# orpheus_esp.net
KiCad netlist of a schematic drawn in EasyEDA Pro
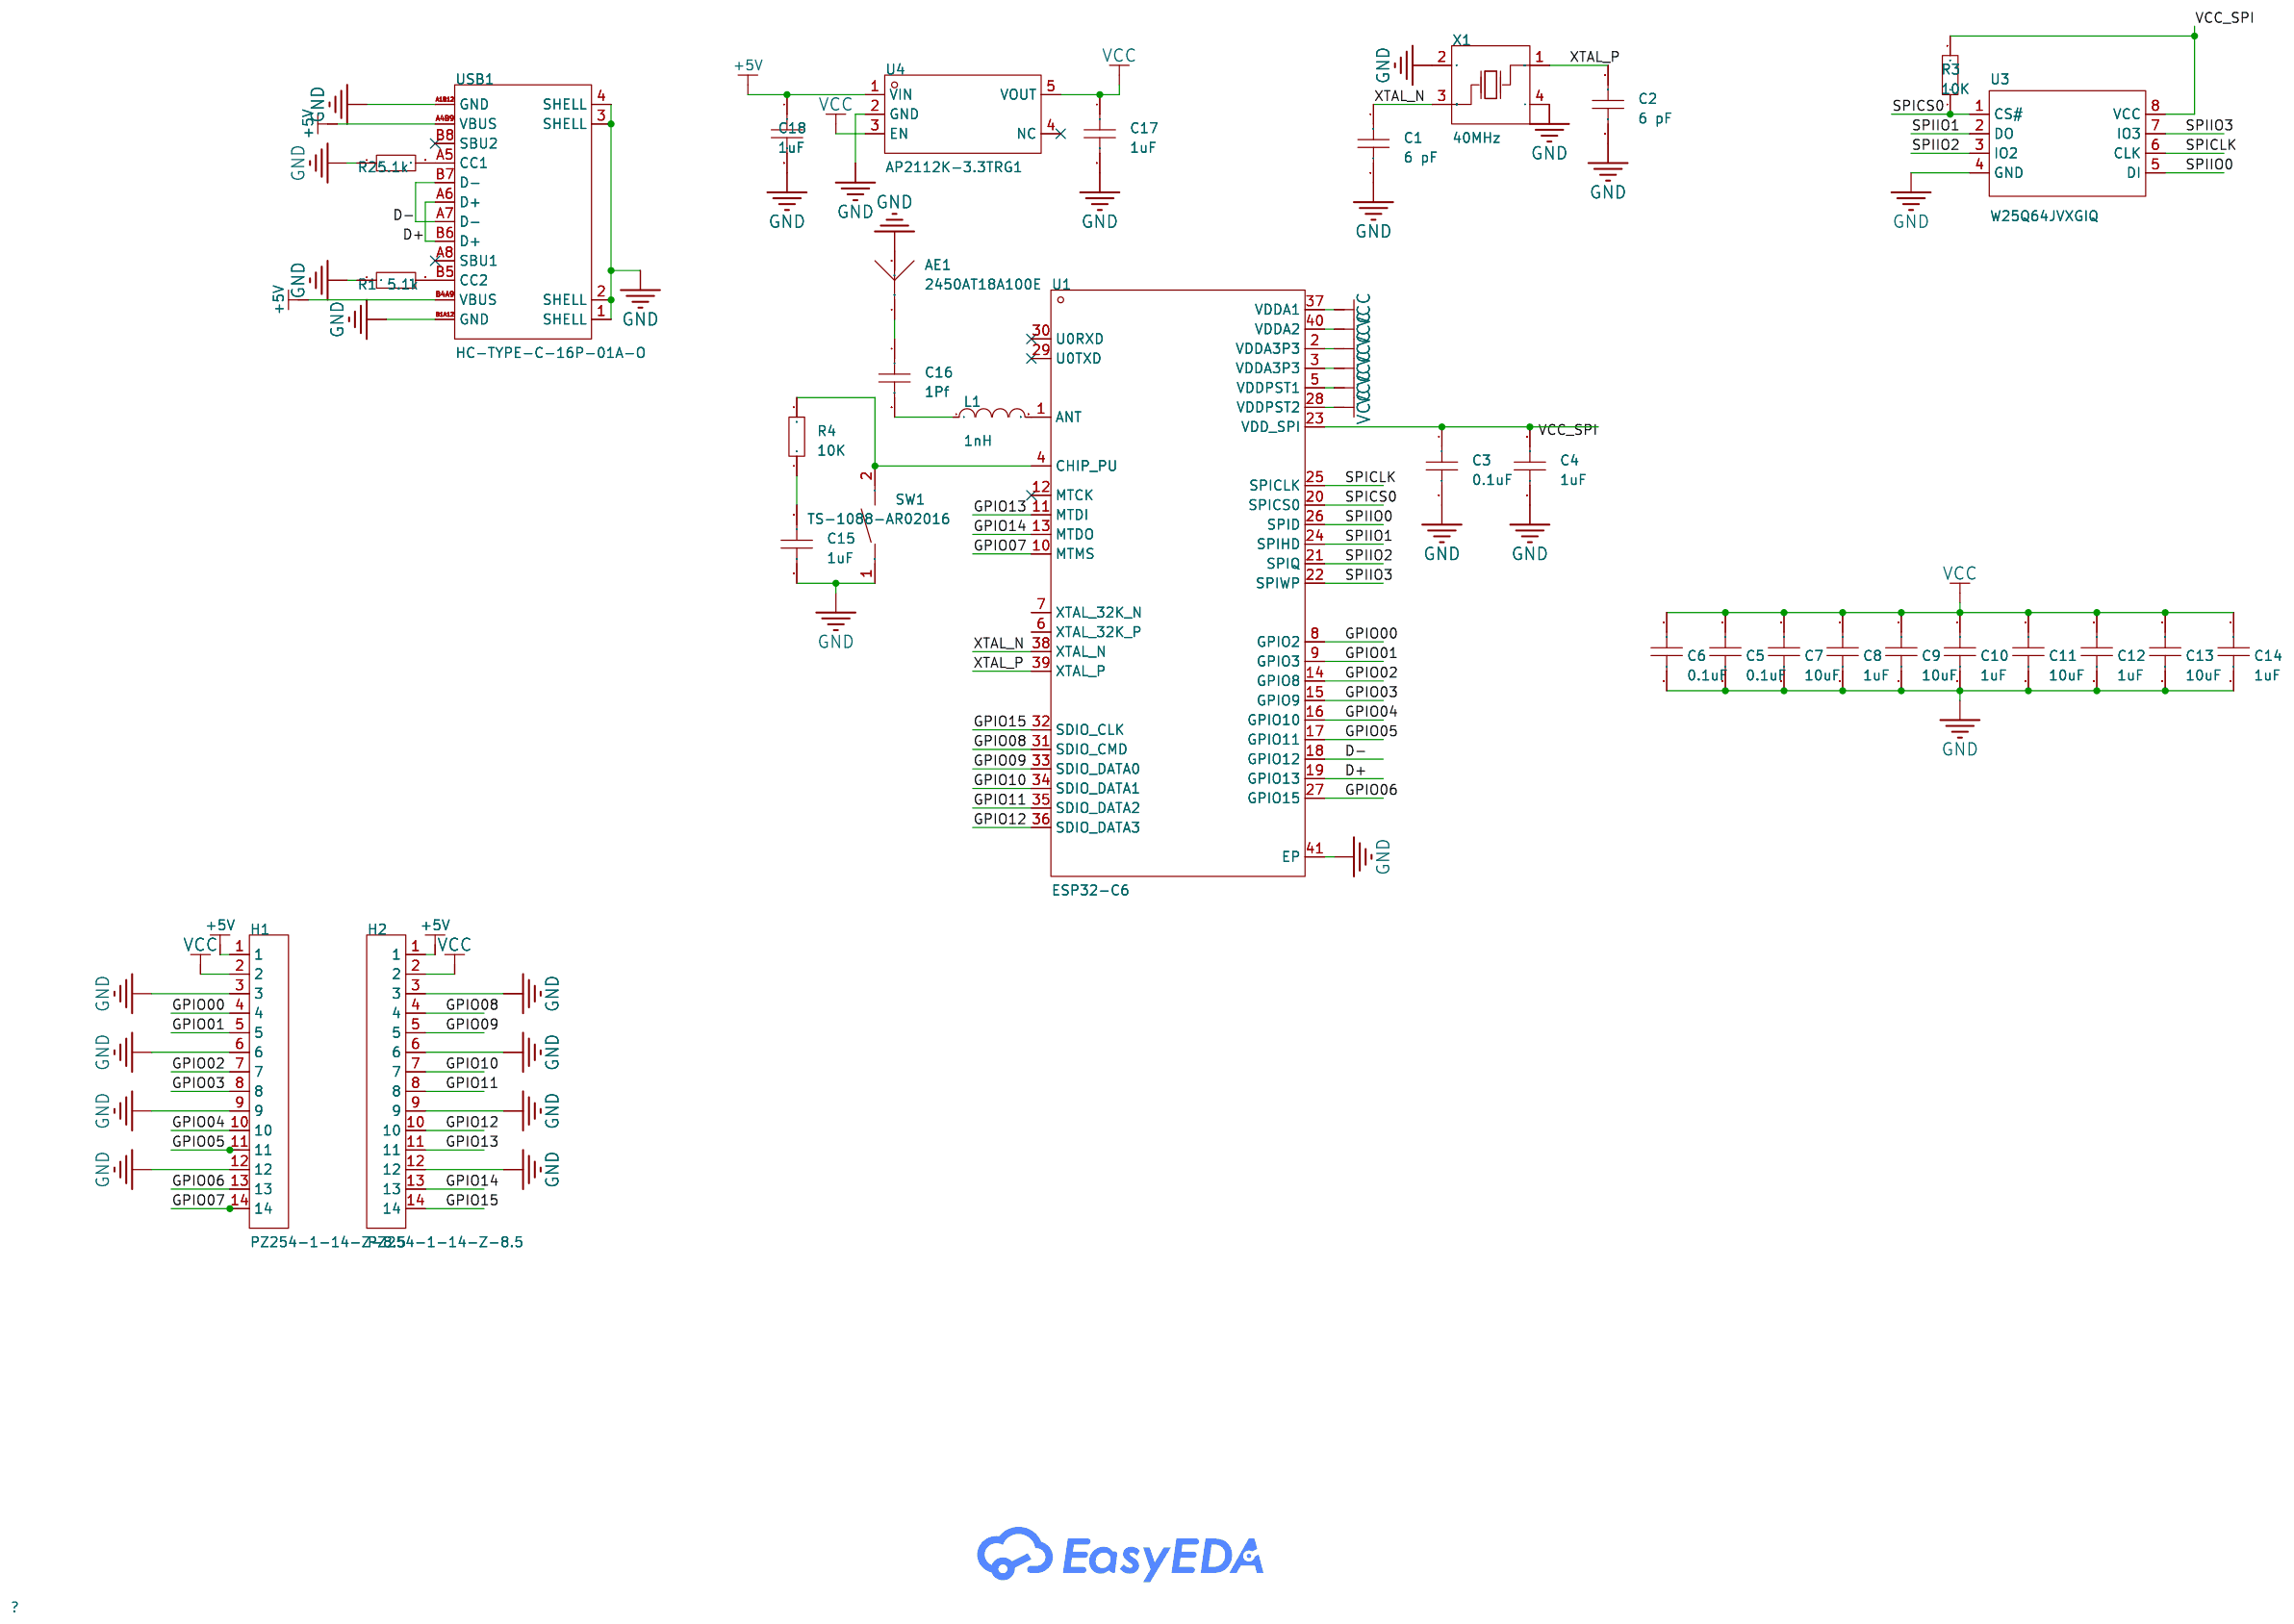
[diagram p0: schematic sheet]

(export (version "E")
  (design (tool "Eeschema 10.0.6"))
  (components
    (comp (ref "AE1")
      (value "2450AT18A100E")
      (footprint "easyedapro:ANT-SMD_L3.2-W1.6")
      (fields (field (name "Manufacturer") "JOHANSON(约翰逊)"))
      (libsource (lib "easyedapro") (part "2450AT18A100E"))
    )
    (comp (ref "C1")
      (value "6 pF")
      (footprint "easyedapro:C0603")
      (libsource (lib "easyedapro") (part "CAP"))
    )
    (comp (ref "C2")
      (value "6 pF")
      (footprint "easyedapro:C0603")
      (libsource (lib "easyedapro") (part "CAP"))
    )
    (comp (ref "C3")
      (value "0.1uF")
      (footprint "easyedapro:C0603")
      (libsource (lib "easyedapro") (part "CAP"))
    )
    (comp (ref "C4") (value "1uF") (footprint "easyedapro:C0603") (libsource (lib "easyedapro") (part "CAP")))
    (comp (ref "C5")
      (value "0.1uF")
      (footprint "easyedapro:C0603")
      (libsource (lib "easyedapro") (part "CAP"))
    )
    (comp (ref "C6")
      (value "0.1uF")
      (footprint "easyedapro:C0603")
      (libsource (lib "easyedapro") (part "CAP"))
    )
    (comp (ref "C7")
      (value "10uF")
      (footprint "easyedapro:C0603")
      (libsource (lib "easyedapro") (part "CAP"))
    )
    (comp (ref "C8") (value "1uF") (footprint "easyedapro:C0603") (libsource (lib "easyedapro") (part "CAP")))
    (comp (ref "C9")
      (value "10uF")
      (footprint "easyedapro:C0603")
      (libsource (lib "easyedapro") (part "CAP"))
    )
    (comp (ref "C10")
      (value "1uF")
      (footprint "easyedapro:C0603")
      (libsource (lib "easyedapro") (part "CAP"))
    )
    (comp (ref "C11")
      (value "10uF")
      (footprint "easyedapro:C0603")
      (libsource (lib "easyedapro") (part "CAP"))
    )
    (comp (ref "C12")
      (value "1uF")
      (footprint "easyedapro:C0603")
      (libsource (lib "easyedapro") (part "CAP"))
    )
    (comp (ref "C13")
      (value "10uF")
      (footprint "easyedapro:C0603")
      (libsource (lib "easyedapro") (part "CAP"))
    )
    (comp (ref "C14")
      (value "1uF")
      (footprint "easyedapro:C0603")
      (libsource (lib "easyedapro") (part "CAP"))
    )
    (comp (ref "C15")
      (value "1uF")
      (footprint "easyedapro:C0603")
      (libsource (lib "easyedapro") (part "CAP"))
    )
    (comp (ref "C16")
      (value "1Pf")
      (footprint "easyedapro:C0603")
      (libsource (lib "easyedapro") (part "CAP"))
    )
    (comp (ref "C17")
      (value "1uF")
      (footprint "easyedapro:C0603")
      (libsource (lib "easyedapro") (part "CAP"))
    )
    (comp (ref "C18")
      (value "1uF")
      (footprint "easyedapro:C0603")
      (libsource (lib "easyedapro") (part "CAP"))
    )
    (comp (ref "H1")
      (value "PZ254-1-14-Z-8.5")
      (footprint "easyedapro:HDR-TH_14P-P2.54-V-M")
      (fields (field (name "Manufacturer") "HCTL(华灿天禄)"))
      (libsource (lib "easyedapro") (part "PZ254-1-14-Z-8.5"))
    )
    (comp (ref "H2")
      (value "PZ254-1-14-Z-8.5")
      (footprint "easyedapro:HDR-TH_14P-P2.54-V-M")
      (fields (field (name "Manufacturer") "HCTL(华灿天禄)"))
      (libsource (lib "easyedapro") (part "PZ254-1-14-Z-8.5"))
    )
    (comp (ref "L1") (value "1nH") (footprint "easyedapro:L0603") (libsource (lib "easyedapro") (part "电感")))
    (comp (ref "R1")
      (value "5.1k")
      (footprint "easyedapro:R0603")
      (libsource (lib "easyedapro") (part "Res"))
    )
    (comp (ref "R2")
      (value "5.1k")
      (footprint "easyedapro:R0603")
      (libsource (lib "easyedapro") (part "Res"))
    )
    (comp (ref "R3") (value "10K") (footprint "easyedapro:R0603") (libsource (lib "easyedapro") (part "Res")))
    (comp (ref "R4") (value "10K") (footprint "easyedapro:R0603") (libsource (lib "easyedapro") (part "Res")))
    (comp (ref "SW1")
      (value "TS-1088-AR02016")
      (footprint "easyedapro:SW-SMD_L3.9-W3.0-P4.45")
      (fields (field (name "Manufacturer") "XUNPU(讯普)"))
      (libsource (lib "easyedapro") (part "TS-1088-AR02016"))
    )
    (comp (ref "U1")
      (value "ESP32-C6")
      (footprint "easyedapro:QFN-40_L5.0-W5.0-P0.40-TL-EP3.3")
      (fields (field (name "Manufacturer") "ESPRESSIF(乐鑫)"))
      (libsource (lib "easyedapro") (part "ESP32-C6_C5364646"))
    )
    (comp (ref "U3")
      (value "W25Q64JVXGIQ")
      (footprint "easyedapro:SOP-8_L5.3-W5.3-P1.27-LS8.0-BL")
      (fields (field (name "Manufacturer") "Winbond(华邦)"))
      (libsource (lib "easyedapro") (part "W25Q64JVSSIQ"))
    )
    (comp (ref "U4")
      (value "AP2112K-3.3TRG1")
      (footprint "easyedapro:SOT-25-5_L2.9-W1.6-P0.95-LS2.8-BL")
      (fields (field (name "Manufacturer") "DIODES(美台)"))
      (libsource (lib "easyedapro") (part "AP2112K-3.3TRG1"))
    )
    (comp (ref "USB1")
      (value "HC-TYPE-C-16P-01A-O")
      (footprint "easyedapro:USB-C-SMD_G-SWITCH_GT-USB-7010EN")
      (fields (field (name "Manufacturer") "HCTL(华灿天禄)"))
      (libsource (lib "easyedapro") (part "HC-TYPE-C-16P-01A-O"))
    )
    (comp (ref "X1")
      (value "40MHz")
      (footprint "easyedapro:CRYSTAL-SMD_4P-L2.0-W1.6-BL")
      (fields (field (name "Manufacturer Part") "Q22FA12800101") (field (name "Manufacturer") "EPSON(爱普生)"))
      (libsource (lib "easyedapro") (part "Q22FA12800101"))
    )
  )
  (nets
    (net (code "1") (name "+5V") (class "Default")
      (node (ref "C18") (pin "1") (pinfunction "1_1") (pintype "input"))
      (node (ref "H1") (pin "1") (pinfunction "1_1") (pintype "unspecified"))
      (node (ref "H2") (pin "1") (pinfunction "1_1") (pintype "unspecified"))
      (node (ref "U4") (pin "1") (pinfunction "VIN_1") (pintype "unspecified"))
      (node (ref "USB1") (pin "A4B9") (pinfunction "VBUS_A4B9") (pintype "unspecified"))
      (node (ref "USB1") (pin "B4A9") (pinfunction "VBUS_B4A9") (pintype "unspecified"))
    )
    (net (code "2") (name "/D+") (class "Default")
      (node (ref "U1") (pin "19") (pinfunction "GPIO13_19") (pintype "unspecified"))
      (node (ref "USB1") (pin "A6") (pinfunction "D+_A6") (pintype "unspecified"))
      (node (ref "USB1") (pin "B6") (pinfunction "D+_B6") (pintype "unspecified"))
    )
    (net (code "3") (name "/D-") (class "Default")
      (node (ref "U1") (pin "18") (pinfunction "GPIO12_18") (pintype "unspecified"))
      (node (ref "USB1") (pin "A7") (pinfunction "D-_A7") (pintype "unspecified"))
      (node (ref "USB1") (pin "B7") (pinfunction "D-_B7") (pintype "unspecified"))
    )
    (net (code "4") (name "/GPIO00") (class "Default")
      (node (ref "H1") (pin "4") (pinfunction "4_4") (pintype "unspecified"))
      (node (ref "U1") (pin "8") (pinfunction "GPIO2_8") (pintype "unspecified"))
    )
    (net (code "5") (name "/GPIO01") (class "Default")
      (node (ref "H1") (pin "5") (pinfunction "5_5") (pintype "unspecified"))
      (node (ref "U1") (pin "9") (pinfunction "GPIO3_9") (pintype "unspecified"))
    )
    (net (code "6") (name "/GPIO02") (class "Default")
      (node (ref "H1") (pin "7") (pinfunction "7_7") (pintype "unspecified"))
      (node (ref "U1") (pin "14") (pinfunction "GPIO8_14") (pintype "unspecified"))
    )
    (net (code "7") (name "/GPIO03") (class "Default")
      (node (ref "H1") (pin "8") (pinfunction "8_8") (pintype "unspecified"))
      (node (ref "U1") (pin "15") (pinfunction "GPIO9_15") (pintype "unspecified"))
    )
    (net (code "8") (name "/GPIO04") (class "Default")
      (node (ref "H1") (pin "10") (pinfunction "10_10") (pintype "unspecified"))
      (node (ref "U1") (pin "16") (pinfunction "GPIO10_16") (pintype "unspecified"))
    )
    (net (code "9") (name "/GPIO05") (class "Default")
      (node (ref "H1") (pin "11") (pinfunction "11_11") (pintype "unspecified"))
      (node (ref "U1") (pin "17") (pinfunction "GPIO11_17") (pintype "unspecified"))
    )
    (net (code "10") (name "/GPIO06") (class "Default")
      (node (ref "H1") (pin "13") (pinfunction "13_13") (pintype "unspecified"))
      (node (ref "U1") (pin "27") (pinfunction "GPIO15_27") (pintype "unspecified"))
    )
    (net (code "11") (name "/GPIO07") (class "Default")
      (node (ref "H1") (pin "14") (pinfunction "14_14") (pintype "unspecified"))
      (node (ref "U1") (pin "10") (pinfunction "MTMS_10") (pintype "unspecified"))
    )
    (net (code "12") (name "/GPIO08") (class "Default")
      (node (ref "H2") (pin "4") (pinfunction "4_4") (pintype "unspecified"))
      (node (ref "U1") (pin "31") (pinfunction "SDIO_CMD_31") (pintype "unspecified"))
    )
    (net (code "13") (name "/GPIO09") (class "Default")
      (node (ref "H2") (pin "5") (pinfunction "5_5") (pintype "unspecified"))
      (node (ref "U1") (pin "33") (pinfunction "SDIO_DATA0_33") (pintype "unspecified"))
    )
    (net (code "14") (name "/GPIO10") (class "Default")
      (node (ref "H2") (pin "7") (pinfunction "7_7") (pintype "unspecified"))
      (node (ref "U1") (pin "34") (pinfunction "SDIO_DATA1_34") (pintype "unspecified"))
    )
    (net (code "15") (name "/GPIO11") (class "Default")
      (node (ref "H2") (pin "8") (pinfunction "8_8") (pintype "unspecified"))
      (node (ref "U1") (pin "35") (pinfunction "SDIO_DATA2_35") (pintype "unspecified"))
    )
    (net (code "16") (name "/GPIO12") (class "Default")
      (node (ref "H2") (pin "10") (pinfunction "10_10") (pintype "unspecified"))
      (node (ref "U1") (pin "36") (pinfunction "SDIO_DATA3_36") (pintype "unspecified"))
    )
    (net (code "17") (name "/GPIO13") (class "Default")
      (node (ref "H2") (pin "11") (pinfunction "11_11") (pintype "unspecified"))
      (node (ref "U1") (pin "11") (pinfunction "MTDI_11") (pintype "unspecified"))
    )
    (net (code "18") (name "/GPIO14") (class "Default")
      (node (ref "H2") (pin "13") (pinfunction "13_13") (pintype "unspecified"))
      (node (ref "U1") (pin "13") (pinfunction "MTDO_13") (pintype "unspecified"))
    )
    (net (code "19") (name "/GPIO15") (class "Default")
      (node (ref "H2") (pin "14") (pinfunction "14_14") (pintype "unspecified"))
      (node (ref "U1") (pin "32") (pinfunction "SDIO_CLK_32") (pintype "unspecified"))
    )
    (net (code "20") (name "/SPICLK") (class "Default")
      (node (ref "U1") (pin "25") (pinfunction "SPICLK_25") (pintype "unspecified"))
      (node (ref "U3") (pin "6") (pinfunction "CLK_6") (pintype "unspecified"))
    )
    (net (code "21") (name "/SPICS0") (class "Default")
      (node (ref "R3") (pin "1") (pinfunction "1_1") (pintype "input"))
      (node (ref "U1") (pin "20") (pinfunction "SPICS0_20") (pintype "unspecified"))
      (node (ref "U3") (pin "1") (pinfunction "CS#_1") (pintype "unspecified"))
    )
    (net (code "22") (name "/SPIIO0") (class "Default")
      (node (ref "U1") (pin "26") (pinfunction "SPID_26") (pintype "unspecified"))
      (node (ref "U3") (pin "5") (pinfunction "DI_5") (pintype "unspecified"))
    )
    (net (code "23") (name "/SPIIO1") (class "Default")
      (node (ref "U1") (pin "24") (pinfunction "SPIHD_24") (pintype "unspecified"))
      (node (ref "U3") (pin "2") (pinfunction "DO_2") (pintype "unspecified"))
    )
    (net (code "24") (name "/SPIIO2") (class "Default")
      (node (ref "U1") (pin "21") (pinfunction "SPIQ_21") (pintype "unspecified"))
      (node (ref "U3") (pin "3") (pinfunction "IO2_3") (pintype "unspecified"))
    )
    (net (code "25") (name "/SPIIO3") (class "Default")
      (node (ref "U1") (pin "22") (pinfunction "SPIWP_22") (pintype "unspecified"))
      (node (ref "U3") (pin "7") (pinfunction "IO3_7") (pintype "unspecified"))
    )
    (net (code "26") (name "/VCC_SPI") (class "Default")
      (node (ref "C3") (pin "1") (pinfunction "1_1") (pintype "input"))
      (node (ref "C4") (pin "2") (pinfunction "2_2") (pintype "input"))
      (node (ref "R3") (pin "2") (pinfunction "2_2") (pintype "input"))
      (node (ref "U1") (pin "23") (pinfunction "VDD_SPI_23") (pintype "unspecified"))
      (node (ref "U3") (pin "8") (pinfunction "VCC_8") (pintype "unspecified"))
    )
    (net (code "27") (name "/XTAL_N") (class "Default")
      (node (ref "C1") (pin "1") (pinfunction "1_1") (pintype "input"))
      (node (ref "U1") (pin "38") (pinfunction "XTAL_N_38") (pintype "unspecified"))
      (node (ref "X1") (pin "3") (pinfunction "OSC2_3") (pintype "unspecified"))
    )
    (net (code "28") (name "/XTAL_P") (class "Default")
      (node (ref "C2") (pin "1") (pinfunction "1_1") (pintype "input"))
      (node (ref "U1") (pin "39") (pinfunction "XTAL_P_39") (pintype "unspecified"))
      (node (ref "X1") (pin "1") (pinfunction "OSC1_1") (pintype "unspecified"))
    )
    (net (code "29") (name "GND") (class "Default")
      (node (ref "AE1") (pin "2") (pinfunction "2_2") (pintype "input"))
      (node (ref "C1") (pin "2") (pinfunction "2_2") (pintype "input"))
      (node (ref "C10") (pin "2") (pinfunction "2_2") (pintype "input"))
      (node (ref "C11") (pin "2") (pinfunction "2_2") (pintype "input"))
      (node (ref "C12") (pin "2") (pinfunction "2_2") (pintype "input"))
      (node (ref "C13") (pin "2") (pinfunction "2_2") (pintype "input"))
      (node (ref "C14") (pin "2") (pinfunction "2_2") (pintype "input"))
      (node (ref "C15") (pin "2") (pinfunction "2_2") (pintype "input"))
      (node (ref "C17") (pin "2") (pinfunction "2_2") (pintype "input"))
      (node (ref "C18") (pin "2") (pinfunction "2_2") (pintype "input"))
      (node (ref "C2") (pin "2") (pinfunction "2_2") (pintype "input"))
      (node (ref "C3") (pin "2") (pinfunction "2_2") (pintype "input"))
      (node (ref "C4") (pin "1") (pinfunction "1_1") (pintype "input"))
      (node (ref "C5") (pin "2") (pinfunction "2_2") (pintype "input"))
      (node (ref "C6") (pin "2") (pinfunction "2_2") (pintype "input"))
      (node (ref "C7") (pin "2") (pinfunction "2_2") (pintype "input"))
      (node (ref "C8") (pin "2") (pinfunction "2_2") (pintype "input"))
      (node (ref "C9") (pin "2") (pinfunction "2_2") (pintype "input"))
      (node (ref "H1") (pin "12") (pinfunction "12_12") (pintype "unspecified"))
      (node (ref "H1") (pin "3") (pinfunction "3_3") (pintype "unspecified"))
      (node (ref "H1") (pin "6") (pinfunction "6_6") (pintype "unspecified"))
      (node (ref "H1") (pin "9") (pinfunction "9_9") (pintype "unspecified"))
      (node (ref "H2") (pin "12") (pinfunction "12_12") (pintype "unspecified"))
      (node (ref "H2") (pin "3") (pinfunction "3_3") (pintype "unspecified"))
      (node (ref "H2") (pin "6") (pinfunction "6_6") (pintype "unspecified"))
      (node (ref "H2") (pin "9") (pinfunction "9_9") (pintype "unspecified"))
      (node (ref "R1") (pin "1") (pinfunction "1_1") (pintype "input"))
      (node (ref "R2") (pin "1") (pinfunction "1_1") (pintype "input"))
      (node (ref "SW1") (pin "1") (pinfunction "1_1") (pintype "unspecified"))
      (node (ref "U1") (pin "41") (pinfunction "EP_41") (pintype "unspecified"))
      (node (ref "U3") (pin "4") (pinfunction "GND_4") (pintype "unspecified"))
      (node (ref "U4") (pin "2") (pinfunction "GND_2") (pintype "unspecified"))
      (node (ref "USB1") (pin "1") (pinfunction "SHELL_1") (pintype "unspecified"))
      (node (ref "USB1") (pin "2") (pinfunction "SHELL_2") (pintype "unspecified"))
      (node (ref "USB1") (pin "3") (pinfunction "SHELL_3") (pintype "unspecified"))
      (node (ref "USB1") (pin "4") (pinfunction "SHELL_4") (pintype "unspecified"))
      (node (ref "USB1") (pin "A1B12") (pinfunction "GND_A1B12") (pintype "unspecified"))
      (node (ref "USB1") (pin "B1A12") (pinfunction "GND_B1A12") (pintype "unspecified"))
      (node (ref "X1") (pin "2") (pinfunction "2_2") (pintype "unspecified"))
      (node (ref "X1") (pin "4") (pinfunction "4_4") (pintype "unspecified"))
    )
    (net (code "30") (name "Net-(AE1-ANT)") (class "Default")
      (node (ref "AE1") (pin "1") (pinfunction "ANT_1") (pintype "input"))
      (node (ref "C16") (pin "1") (pinfunction "1_1") (pintype "input"))
    )
    (net (code "31") (name "Net-(C15-Pad1)") (class "Default")
      (node (ref "C15") (pin "1") (pinfunction "1_1") (pintype "input"))
      (node (ref "R4") (pin "1") (pinfunction "1_1") (pintype "input"))
    )
    (net (code "32") (name "Net-(C16-Pad2)") (class "Default")
      (node (ref "C16") (pin "2") (pinfunction "2_2") (pintype "input"))
      (node (ref "L1") (pin "1") (pinfunction "1_1") (pintype "input"))
    )
    (net (code "33") (name "Net-(U1-ANT)") (class "Default")
      (node (ref "L1") (pin "2") (pinfunction "2_2") (pintype "input"))
      (node (ref "U1") (pin "1") (pinfunction "ANT_1") (pintype "unspecified"))
    )
    (net (code "34") (name "Net-(U1-CHIP_PU)") (class "Default")
      (node (ref "R4") (pin "2") (pinfunction "2_2") (pintype "input"))
      (node (ref "SW1") (pin "2") (pinfunction "2_2") (pintype "unspecified"))
      (node (ref "U1") (pin "4") (pinfunction "CHIP_PU_4") (pintype "unspecified"))
    )
    (net (code "35") (name "Net-(USB1-CC1)") (class "Default")
      (node (ref "R2") (pin "2") (pinfunction "2_2") (pintype "input"))
      (node (ref "USB1") (pin "A5") (pinfunction "CC1_A5") (pintype "unspecified"))
    )
    (net (code "36") (name "Net-(USB1-CC2)") (class "Default")
      (node (ref "R1") (pin "2") (pinfunction "2_2") (pintype "input"))
      (node (ref "USB1") (pin "B5") (pinfunction "CC2_B5") (pintype "unspecified"))
    )
    (net (code "37") (name "VCC") (class "Default")
      (node (ref "C10") (pin "1") (pinfunction "1_1") (pintype "input"))
      (node (ref "C11") (pin "1") (pinfunction "1_1") (pintype "input"))
      (node (ref "C12") (pin "1") (pinfunction "1_1") (pintype "input"))
      (node (ref "C13") (pin "1") (pinfunction "1_1") (pintype "input"))
      (node (ref "C14") (pin "1") (pinfunction "1_1") (pintype "input"))
      (node (ref "C17") (pin "1") (pinfunction "1_1") (pintype "input"))
      (node (ref "C5") (pin "1") (pinfunction "1_1") (pintype "input"))
      (node (ref "C6") (pin "1") (pinfunction "1_1") (pintype "input"))
      (node (ref "C7") (pin "1") (pinfunction "1_1") (pintype "input"))
      (node (ref "C8") (pin "1") (pinfunction "1_1") (pintype "input"))
      (node (ref "C9") (pin "1") (pinfunction "1_1") (pintype "input"))
      (node (ref "H1") (pin "2") (pinfunction "2_2") (pintype "unspecified"))
      (node (ref "H2") (pin "2") (pinfunction "2_2") (pintype "unspecified"))
      (node (ref "U1") (pin "2") (pinfunction "VDDA3P3_2") (pintype "unspecified"))
      (node (ref "U1") (pin "28") (pinfunction "VDDPST2_28") (pintype "unspecified"))
      (node (ref "U1") (pin "3") (pinfunction "VDDA3P3_3") (pintype "unspecified"))
      (node (ref "U1") (pin "37") (pinfunction "VDDA1_37") (pintype "unspecified"))
      (node (ref "U1") (pin "40") (pinfunction "VDDA2_40") (pintype "unspecified"))
      (node (ref "U1") (pin "5") (pinfunction "VDDPST1_5") (pintype "unspecified"))
      (node (ref "U4") (pin "3") (pinfunction "EN_3") (pintype "unspecified"))
      (node (ref "U4") (pin "5") (pinfunction "VOUT_5") (pintype "unspecified"))
    )
    (net (code "38") (name "unconnected-(U1-MTCK-Pad12)") (class "Default")
      (node (ref "U1") (pin "12") (pinfunction "MTCK_12") (pintype "unspecified+no_connect"))
    )
    (net (code "39") (name "unconnected-(U1-U0RXD-Pad30)") (class "Default")
      (node (ref "U1") (pin "30") (pinfunction "U0RXD_30") (pintype "unspecified+no_connect"))
    )
    (net (code "40") (name "unconnected-(U1-U0TXD-Pad29)") (class "Default")
      (node (ref "U1") (pin "29") (pinfunction "U0TXD_29") (pintype "unspecified+no_connect"))
    )
    (net (code "41") (name "unconnected-(U1-XTAL_32K_N-Pad7)") (class "Default")
      (node (ref "U1") (pin "7") (pinfunction "XTAL_32K_N_7") (pintype "unspecified"))
    )
    (net (code "42") (name "unconnected-(U1-XTAL_32K_P-Pad6)") (class "Default")
      (node (ref "U1") (pin "6") (pinfunction "XTAL_32K_P_6") (pintype "unspecified"))
    )
    (net (code "43") (name "unconnected-(U4-NC-Pad4)") (class "Default")
      (node (ref "U4") (pin "4") (pinfunction "NC_4") (pintype "unspecified+no_connect"))
    )
    (net (code "44") (name "unconnected-(USB1-SBU1-PadA8)") (class "Default")
      (node (ref "USB1") (pin "A8") (pinfunction "SBU1_A8") (pintype "unspecified+no_connect"))
    )
    (net (code "45") (name "unconnected-(USB1-SBU2-PadB8)") (class "Default")
      (node (ref "USB1") (pin "B8") (pinfunction "SBU2_B8") (pintype "unspecified+no_connect"))
    )
  )
)
